# Sheet1.net
KiCad netlist of a schematic drawn in Altium Designer
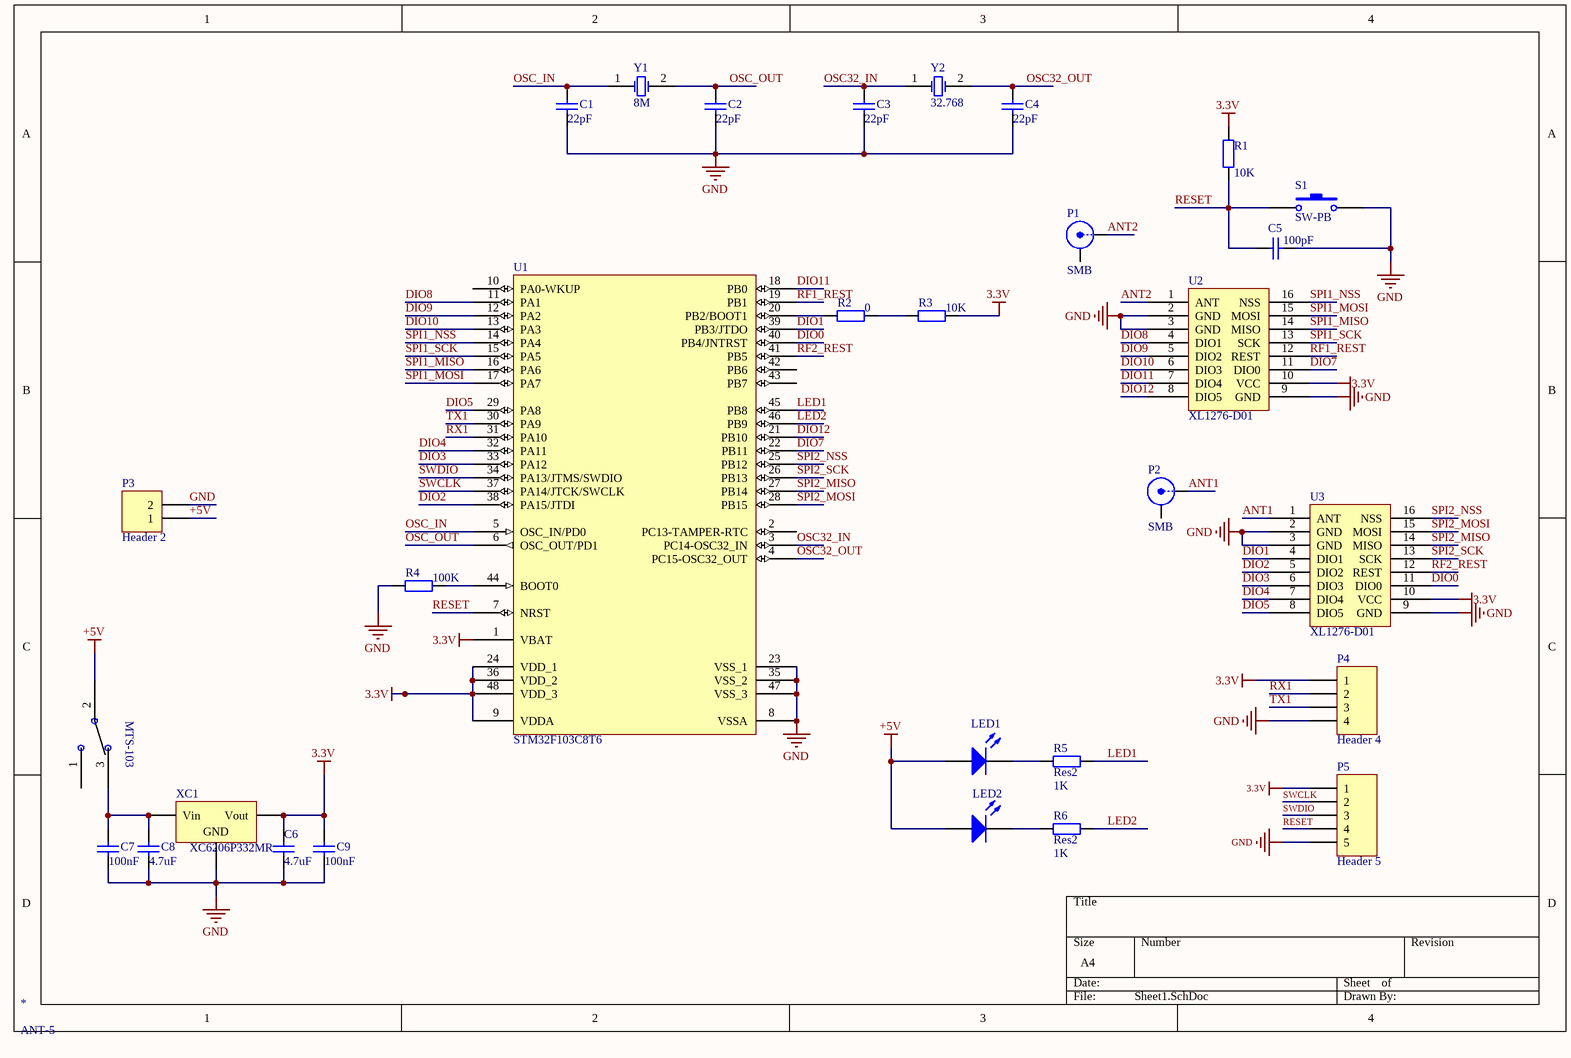
[diagram p0: Sheet1.SchDoc]

(export (version "E")
  (design (tool "Eeschema 10.0.6"))
  (components
    (comp (ref "*") (value "ANT-5") (libsource (lib "Schlib1") (part "ANT-5")))
    (comp (ref "C1")
      (value "22pF")
      (footprint "1608[0603]")
      (description "Capacitor (Semiconductor SIM Model)")
      (fields (field (name "Comment") "Cap Semi") (field (name "PUBLISHER") "Altium Limited"))
      (libsource (lib "Miscellaneous Devices") (part "Cap Semi"))
    )
    (comp (ref "C2")
      (value "22pF")
      (footprint "1608[0603]")
      (description "Capacitor (Semiconductor SIM Model)")
      (fields (field (name "Comment") "Cap Semi") (field (name "PUBLISHER") "Altium Limited"))
      (libsource (lib "Miscellaneous Devices") (part "Cap Semi"))
    )
    (comp (ref "C3")
      (value "22pF")
      (footprint "1608[0603]")
      (description "Capacitor (Semiconductor SIM Model)")
      (fields (field (name "Comment") "Cap Semi") (field (name "PUBLISHER") "Altium Limited"))
      (libsource (lib "Miscellaneous Devices") (part "Cap Semi"))
    )
    (comp (ref "C4")
      (value "22pF")
      (footprint "1608[0603]")
      (description "Capacitor (Semiconductor SIM Model)")
      (fields (field (name "Comment") "Cap Semi") (field (name "PUBLISHER") "Altium Limited"))
      (libsource (lib "Miscellaneous Devices") (part "Cap Semi"))
    )
    (comp (ref "C5")
      (value "100pF")
      (footprint "1608[0603]")
      (description "Capacitor (Semiconductor SIM Model)")
      (fields (field (name "Comment") "Cap Semi") (field (name "PUBLISHER") "Altium Limited"))
      (libsource (lib "Miscellaneous Devices") (part "Cap Semi"))
    )
    (comp (ref "C6")
      (value "4.7uF")
      (footprint "1608[0603]")
      (description "Capacitor (Semiconductor SIM Model)")
      (fields (field (name "Comment") "Cap Semi") (field (name "PUBLISHER") "Altium Limited"))
      (libsource (lib "Miscellaneous Devices") (part "Cap Semi"))
    )
    (comp (ref "C7")
      (value "100nF")
      (footprint "1608[0603]")
      (description "Capacitor (Semiconductor SIM Model)")
      (fields (field (name "Comment") "Cap Semi") (field (name "PUBLISHER") "Altium Limited"))
      (libsource (lib "Miscellaneous Devices") (part "Cap Semi"))
    )
    (comp (ref "C8")
      (value "4.7uF")
      (footprint "1608[0603]")
      (description "Capacitor (Semiconductor SIM Model)")
      (fields (field (name "Comment") "Cap Semi") (field (name "PUBLISHER") "Altium Limited"))
      (libsource (lib "Miscellaneous Devices") (part "Cap Semi"))
    )
    (comp (ref "C9")
      (value "100nF")
      (footprint "1608[0603]")
      (description "Capacitor (Semiconductor SIM Model)")
      (fields (field (name "Comment") "Cap Semi") (field (name "PUBLISHER") "Altium Limited"))
      (libsource (lib "Miscellaneous Devices") (part "Cap Semi"))
    )
    (comp (ref "LED1")
      (value "LED2")
      (footprint "3.2X1.6X1.1")
      (description "Typical RED, GREEN, YELLOW, AMBER GaAs LED")
      (fields (field (name "PUBLISHER") "Altium Limited"))
      (libsource (lib "Miscellaneous Devices") (part "LED2"))
    )
    (comp (ref "LED2")
      (value "LED2")
      (footprint "3.2X1.6X1.1")
      (description "Typical RED, GREEN, YELLOW, AMBER GaAs LED")
      (fields (field (name "PUBLISHER") "Altium Limited"))
      (libsource (lib "Miscellaneous Devices") (part "LED2"))
    )
    (comp (ref "MTS-1")
      (value "MTS-103")
      (footprint "PcbLib1:MTS-103")
      (libsource (lib "Schlib1") (part "MTS-103"))
    )
    (comp (ref "P1")
      (value "SMB")
      (footprint "SMB_V-RJ45")
      (description "SMB Straight Connector")
      (fields (field (name "PUBLISHER") "Altium Limited"))
      (libsource (lib "Miscellaneous Connectors") (part "SMB"))
    )
    (comp (ref "P2")
      (value "SMB")
      (footprint "SMB_V-RJ45")
      (description "SMB Straight Connector")
      (fields (field (name "PUBLISHER") "Altium Limited"))
      (libsource (lib "Miscellaneous Connectors") (part "SMB"))
    )
    (comp (ref "P3")
      (value "Header 2")
      (footprint "HDR1X2")
      (description "Header, 2-Pin")
      (fields (field (name "PUBLISHER") "Altium Limited"))
      (libsource (lib "Miscellaneous Connectors") (part "Header 2"))
    )
    (comp (ref "P4")
      (value "Header 4")
      (footprint "HDR1X4")
      (description "Header, 4-Pin")
      (fields (field (name "PUBLISHER") "Altium Limited"))
      (libsource (lib "Miscellaneous Connectors") (part "Header 4"))
    )
    (comp (ref "P5")
      (value "Header 5")
      (footprint "HDR1X5")
      (description "Header, 5-Pin")
      (fields (field (name "PUBLISHER") "Altium Limited"))
      (libsource (lib "Miscellaneous Connectors") (part "Header 5"))
    )
    (comp (ref "R1")
      (value "10K")
      (footprint "1608[0603]")
      (description "Resistor")
      (fields (field (name "Comment") "Res2") (field (name "PUBLISHER") "Altium Limited"))
      (libsource (lib "") (part "Res2_1"))
    )
    (comp (ref "R2")
      (value "0")
      (footprint "1608[0603]")
      (description "Resistor")
      (fields (field (name "Comment") "Res2") (field (name "PUBLISHER") "Altium Limited"))
      (libsource (lib "Miscellaneous Devices") (part "Res2"))
    )
    (comp (ref "R3")
      (value "10K")
      (footprint "1608[0603]")
      (description "Resistor")
      (fields (field (name "Comment") "Res2") (field (name "PUBLISHER") "Altium Limited"))
      (libsource (lib "Miscellaneous Devices") (part "Res2"))
    )
    (comp (ref "R4")
      (value "100K")
      (footprint "1608[0603]")
      (description "Resistor")
      (fields (field (name "Comment") "Res2") (field (name "PUBLISHER") "Altium Limited"))
      (libsource (lib "Miscellaneous Devices") (part "Res2"))
    )
    (comp (ref "R5")
      (value "Res2")
      (footprint "1608[0603]")
      (description "Resistor")
      (fields (field (name "ALTIUM_VALUE") "1K") (field (name "PUBLISHER") "Altium Limited"))
      (libsource (lib "Miscellaneous Devices") (part "Res2"))
    )
    (comp (ref "R6")
      (value "Res2")
      (footprint "1608[0603]")
      (description "Resistor")
      (fields (field (name "ALTIUM_VALUE") "1K") (field (name "PUBLISHER") "Altium Limited"))
      (libsource (lib "Miscellaneous Devices") (part "Res2"))
    )
    (comp (ref "S1")
      (value "SW-PB")
      (footprint "SPST-2")
      (description "Switch")
      (fields (field (name "PUBLISHER") "Altium Limited"))
      (libsource (lib "Miscellaneous Devices") (part "SW-PB"))
    )
    (comp (ref "U1")
      (value "STM32F103C8T6")
      (footprint "LQFP48_N")
      (description "STM32 ARM-based 32-bit MCU with 64 Kbytes Flash, 48-pin LQFP, Industrial Temperature")
      (fields (field (name "PUBLISHER") "Altium Limited"))
      (libsource (lib "ST Microcontroller 32-Bit STM32") (part "STM32F103C8T6"))
    )
    (comp (ref "U2")
      (value "XL1276-D01")
      (footprint "XL1278-DO1")
      (libsource (lib "Schlib1") (part "XL1276-D01"))
    )
    (comp (ref "U3")
      (value "XL1276-D01")
      (footprint "XL1278-DO1")
      (libsource (lib "Schlib1") (part "XL1276-D01"))
    )
    (comp (ref "XC1")
      (value "XC6206P332MR")
      (footprint "SOT89L")
      (description "Voltage Regulator")
      (fields (field (name "PUBLISHER") "Altium Limited"))
      (libsource (lib "Miscellaneous Devices") (part "Volt Reg"))
    )
    (comp (ref "Y1")
      (value "8M")
      (footprint "HC-48SMD")
      (description "Crystal Oscillator")
      (fields (field (name "PUBLISHER") "Altium Limited"))
      (libsource (lib "Miscellaneous Devices") (part "XTAL"))
    )
    (comp (ref "Y2")
      (value "32.768")
      (footprint "FC135")
      (description "Crystal Oscillator")
      (fields (field (name "PUBLISHER") "Altium Limited"))
      (libsource (lib "Miscellaneous Devices") (part "XTAL"))
    )
  )
  (nets
    (net (code "1") (name "+5V") (class "Default")
      (node (ref "LED1") (pin "1") (pinfunction "A_1") (pintype "passive"))
      (node (ref "LED2") (pin "1") (pinfunction "A_1") (pintype "passive"))
      (node (ref "MTS-1") (pin "2") (pinfunction "2_2") (pintype "passive"))
      (node (ref "P3") (pin "1") (pinfunction "1_1") (pintype "passive"))
    )
    (net (code "2") (name "/ANT1") (class "Default")
      (node (ref "P2") (pin "1") (pinfunction "X_1") (pintype "passive"))
      (node (ref "U3") (pin "1") (pinfunction "ANT_1") (pintype "passive"))
    )
    (net (code "3") (name "/ANT2") (class "Default")
      (node (ref "P1") (pin "1") (pinfunction "X_1") (pintype "passive"))
      (node (ref "U2") (pin "1") (pinfunction "ANT_1") (pintype "passive"))
    )
    (net (code "4") (name "/DIO0") (class "Default")
      (node (ref "U1") (pin "40") (pinfunction "PB4/JNTRST_40") (pintype "bidirectional"))
      (node (ref "U3") (pin "11") (pinfunction "DIO0_11") (pintype "passive"))
    )
    (net (code "5") (name "/DIO1") (class "Default")
      (node (ref "U1") (pin "39") (pinfunction "PB3/JTDO_39") (pintype "bidirectional"))
      (node (ref "U3") (pin "4") (pinfunction "DIO1_4") (pintype "passive"))
    )
    (net (code "6") (name "/DIO2") (class "Default")
      (node (ref "U1") (pin "38") (pinfunction "PA15/JTDI_38") (pintype "bidirectional"))
      (node (ref "U3") (pin "5") (pinfunction "DIO2_5") (pintype "passive"))
    )
    (net (code "7") (name "/DIO3") (class "Default")
      (node (ref "U1") (pin "33") (pinfunction "PA12_33") (pintype "bidirectional"))
      (node (ref "U3") (pin "6") (pinfunction "DIO3_6") (pintype "passive"))
    )
    (net (code "8") (name "/DIO4") (class "Default")
      (node (ref "U1") (pin "32") (pinfunction "PA11_32") (pintype "bidirectional"))
      (node (ref "U3") (pin "7") (pinfunction "DIO4_7") (pintype "passive"))
    )
    (net (code "9") (name "/DIO5") (class "Default")
      (node (ref "U1") (pin "29") (pinfunction "PA8_29") (pintype "bidirectional"))
      (node (ref "U3") (pin "8") (pinfunction "DIO5_8") (pintype "passive"))
    )
    (net (code "10") (name "/DIO7") (class "Default")
      (node (ref "U1") (pin "22") (pinfunction "PB11_22") (pintype "bidirectional"))
      (node (ref "U2") (pin "11") (pinfunction "DIO0_11") (pintype "passive"))
    )
    (net (code "11") (name "/DIO8") (class "Default")
      (node (ref "U1") (pin "11") (pinfunction "PA1_11") (pintype "bidirectional"))
      (node (ref "U2") (pin "4") (pinfunction "DIO1_4") (pintype "passive"))
    )
    (net (code "12") (name "/DIO9") (class "Default")
      (node (ref "U1") (pin "12") (pinfunction "PA2_12") (pintype "bidirectional"))
      (node (ref "U2") (pin "5") (pinfunction "DIO2_5") (pintype "passive"))
    )
    (net (code "13") (name "/DIO10") (class "Default")
      (node (ref "U1") (pin "13") (pinfunction "PA3_13") (pintype "bidirectional"))
      (node (ref "U2") (pin "6") (pinfunction "DIO3_6") (pintype "passive"))
    )
    (net (code "14") (name "/DIO11") (class "Default")
      (node (ref "U1") (pin "18") (pinfunction "PB0_18") (pintype "bidirectional"))
      (node (ref "U2") (pin "7") (pinfunction "DIO4_7") (pintype "passive"))
    )
    (net (code "15") (name "/DIO12") (class "Default")
      (node (ref "U1") (pin "21") (pinfunction "PB10_21") (pintype "bidirectional"))
      (node (ref "U2") (pin "8") (pinfunction "DIO5_8") (pintype "passive"))
    )
    (net (code "16") (name "/LED1") (class "Default")
      (node (ref "R5") (pin "2") (pinfunction "2_2") (pintype "passive"))
      (node (ref "U1") (pin "45") (pinfunction "PB8_45") (pintype "bidirectional"))
    )
    (net (code "17") (name "/LED2") (class "Default")
      (node (ref "R6") (pin "2") (pinfunction "2_2") (pintype "passive"))
      (node (ref "U1") (pin "46") (pinfunction "PB9_46") (pintype "bidirectional"))
    )
    (net (code "18") (name "/OSC32_IN") (class "Default")
      (node (ref "C3") (pin "2") (pinfunction "2_2") (pintype "passive"))
      (node (ref "U1") (pin "3") (pinfunction "PC14-OSC32_IN_3") (pintype "bidirectional"))
      (node (ref "Y2") (pin "1") (pinfunction "OSC1_1") (pintype "passive"))
    )
    (net (code "19") (name "/OSC32_OUT") (class "Default")
      (node (ref "C4") (pin "2") (pinfunction "2_2") (pintype "passive"))
      (node (ref "U1") (pin "4") (pinfunction "PC15-OSC32_OUT_4") (pintype "bidirectional"))
      (node (ref "Y2") (pin "2") (pinfunction "OSC2_2") (pintype "passive"))
    )
    (net (code "20") (name "/OSC_IN") (class "Default")
      (node (ref "C1") (pin "2") (pinfunction "2_2") (pintype "passive"))
      (node (ref "U1") (pin "5") (pinfunction "OSC_IN/PD0_5") (pintype "input"))
      (node (ref "Y1") (pin "1") (pinfunction "OSC1_1") (pintype "passive"))
    )
    (net (code "21") (name "/OSC_OUT") (class "Default")
      (node (ref "C2") (pin "2") (pinfunction "2_2") (pintype "passive"))
      (node (ref "U1") (pin "6") (pinfunction "OSC_OUT/PD1_6") (pintype "output"))
      (node (ref "Y1") (pin "2") (pinfunction "OSC2_2") (pintype "passive"))
    )
    (net (code "22") (name "/RESET") (class "Default")
      (node (ref "C5") (pin "1") (pinfunction "1_1") (pintype "passive"))
      (node (ref "P5") (pin "4") (pinfunction "4_4") (pintype "passive"))
      (node (ref "R1") (pin "2") (pinfunction "2_2") (pintype "passive"))
      (node (ref "S1") (pin "1") (pinfunction "1_1") (pintype "passive"))
      (node (ref "U1") (pin "7") (pinfunction "NRST_7") (pintype "bidirectional"))
    )
    (net (code "23") (name "/RF1_REST") (class "Default")
      (node (ref "U1") (pin "19") (pinfunction "PB1_19") (pintype "bidirectional"))
      (node (ref "U2") (pin "12") (pinfunction "REST_12") (pintype "passive"))
    )
    (net (code "24") (name "/RF2_REST") (class "Default")
      (node (ref "U1") (pin "41") (pinfunction "PB5_41") (pintype "bidirectional"))
      (node (ref "U3") (pin "12") (pinfunction "REST_12") (pintype "passive"))
    )
    (net (code "25") (name "/RX1") (class "Default")
      (node (ref "P4") (pin "2") (pinfunction "2_2") (pintype "passive"))
      (node (ref "U1") (pin "31") (pinfunction "PA10_31") (pintype "bidirectional"))
    )
    (net (code "26") (name "/SPI1_MISO") (class "Default")
      (node (ref "U1") (pin "16") (pinfunction "PA6_16") (pintype "bidirectional"))
      (node (ref "U2") (pin "14") (pinfunction "MISO_14") (pintype "passive"))
    )
    (net (code "27") (name "/SPI1_MOSI") (class "Default")
      (node (ref "U1") (pin "17") (pinfunction "PA7_17") (pintype "bidirectional"))
      (node (ref "U2") (pin "15") (pinfunction "MOSI_15") (pintype "passive"))
    )
    (net (code "28") (name "/SPI1_NSS") (class "Default")
      (node (ref "U1") (pin "14") (pinfunction "PA4_14") (pintype "bidirectional"))
      (node (ref "U2") (pin "16") (pinfunction "NSS_16") (pintype "passive"))
    )
    (net (code "29") (name "/SPI1_SCK") (class "Default")
      (node (ref "U1") (pin "15") (pinfunction "PA5_15") (pintype "bidirectional"))
      (node (ref "U2") (pin "13") (pinfunction "SCK_13") (pintype "passive"))
    )
    (net (code "30") (name "/SPI2_MISO") (class "Default")
      (node (ref "U1") (pin "27") (pinfunction "PB14_27") (pintype "bidirectional"))
      (node (ref "U3") (pin "14") (pinfunction "MISO_14") (pintype "passive"))
    )
    (net (code "31") (name "/SPI2_MOSI") (class "Default")
      (node (ref "U1") (pin "28") (pinfunction "PB15_28") (pintype "bidirectional"))
      (node (ref "U3") (pin "15") (pinfunction "MOSI_15") (pintype "passive"))
    )
    (net (code "32") (name "/SPI2_NSS") (class "Default")
      (node (ref "U1") (pin "25") (pinfunction "PB12_25") (pintype "bidirectional"))
      (node (ref "U3") (pin "16") (pinfunction "NSS_16") (pintype "passive"))
    )
    (net (code "33") (name "/SPI2_SCK") (class "Default")
      (node (ref "U1") (pin "26") (pinfunction "PB13_26") (pintype "bidirectional"))
      (node (ref "U3") (pin "13") (pinfunction "SCK_13") (pintype "passive"))
    )
    (net (code "34") (name "/SWCLK") (class "Default")
      (node (ref "P5") (pin "2") (pinfunction "2_2") (pintype "passive"))
      (node (ref "U1") (pin "37") (pinfunction "PA14/JTCK/SWCLK_37") (pintype "bidirectional"))
    )
    (net (code "35") (name "/SWDIO") (class "Default")
      (node (ref "P5") (pin "3") (pinfunction "3_3") (pintype "passive"))
      (node (ref "U1") (pin "34") (pinfunction "PA13/JTMS/SWDIO_34") (pintype "bidirectional"))
    )
    (net (code "36") (name "/TX1") (class "Default")
      (node (ref "P4") (pin "3") (pinfunction "3_3") (pintype "passive"))
      (node (ref "U1") (pin "30") (pinfunction "PA9_30") (pintype "bidirectional"))
    )
    (net (code "37") (name "3.3V") (class "Default")
      (node (ref "C6") (pin "2") (pinfunction "2_2") (pintype "passive"))
      (node (ref "C9") (pin "2") (pinfunction "2_2") (pintype "passive"))
      (node (ref "P4") (pin "1") (pinfunction "1_1") (pintype "passive"))
      (node (ref "P5") (pin "1") (pinfunction "1_1") (pintype "passive"))
      (node (ref "R1") (pin "1") (pinfunction "1_1") (pintype "passive"))
      (node (ref "R3") (pin "2") (pinfunction "2_2") (pintype "passive"))
      (node (ref "U1") (pin "1") (pinfunction "VBAT_1") (pintype "power_in"))
      (node (ref "U1") (pin "24") (pinfunction "VDD_1_24") (pintype "power_in"))
      (node (ref "U1") (pin "36") (pinfunction "VDD_2_36") (pintype "power_in"))
      (node (ref "U1") (pin "48") (pinfunction "VDD_3_48") (pintype "power_in"))
      (node (ref "U1") (pin "9") (pinfunction "VDDA_9") (pintype "power_in"))
      (node (ref "U2") (pin "10") (pinfunction "VCC_10") (pintype "passive"))
      (node (ref "U3") (pin "10") (pinfunction "VCC_10") (pintype "passive"))
      (node (ref "XC1") (pin "3") (pinfunction "Vout_3") (pintype "passive"))
    )
    (net (code "38") (name "GND") (class "Default")
      (node (ref "C1") (pin "1") (pinfunction "1_1") (pintype "passive"))
      (node (ref "C2") (pin "1") (pinfunction "1_1") (pintype "passive"))
      (node (ref "C3") (pin "1") (pinfunction "1_1") (pintype "passive"))
      (node (ref "C4") (pin "1") (pinfunction "1_1") (pintype "passive"))
      (node (ref "C5") (pin "2") (pinfunction "2_2") (pintype "passive"))
      (node (ref "C6") (pin "1") (pinfunction "1_1") (pintype "passive"))
      (node (ref "C7") (pin "1") (pinfunction "1_1") (pintype "passive"))
      (node (ref "C8") (pin "1") (pinfunction "1_1") (pintype "passive"))
      (node (ref "C9") (pin "1") (pinfunction "1_1") (pintype "passive"))
      (node (ref "P3") (pin "2") (pinfunction "2_2") (pintype "passive"))
      (node (ref "P4") (pin "4") (pinfunction "4_4") (pintype "passive"))
      (node (ref "P5") (pin "5") (pinfunction "5_5") (pintype "passive"))
      (node (ref "R4") (pin "1") (pinfunction "1_1") (pintype "passive"))
      (node (ref "S1") (pin "2") (pinfunction "2_2") (pintype "passive"))
      (node (ref "U1") (pin "23") (pinfunction "VSS_1_23") (pintype "power_in"))
      (node (ref "U1") (pin "35") (pinfunction "VSS_2_35") (pintype "power_in"))
      (node (ref "U1") (pin "47") (pinfunction "VSS_3_47") (pintype "power_in"))
      (node (ref "U1") (pin "8") (pinfunction "VSSA_8") (pintype "power_in"))
      (node (ref "U2") (pin "2") (pinfunction "GND_2") (pintype "passive"))
      (node (ref "U2") (pin "3") (pinfunction "GND_3") (pintype "passive"))
      (node (ref "U2") (pin "9") (pinfunction "GND_9") (pintype "passive"))
      (node (ref "U3") (pin "2") (pinfunction "GND_2") (pintype "passive"))
      (node (ref "U3") (pin "3") (pinfunction "GND_3") (pintype "passive"))
      (node (ref "U3") (pin "9") (pinfunction "GND_9") (pintype "passive"))
      (node (ref "XC1") (pin "2") (pinfunction "GND_2") (pintype "passive"))
    )
    (net (code "39") (name "Net-(LED1-K)") (class "Default")
      (node (ref "LED1") (pin "2") (pinfunction "K_2") (pintype "passive"))
      (node (ref "R5") (pin "1") (pinfunction "1_1") (pintype "passive"))
    )
    (net (code "40") (name "Net-(LED2-K)") (class "Default")
      (node (ref "LED2") (pin "2") (pinfunction "K_2") (pintype "passive"))
      (node (ref "R6") (pin "1") (pinfunction "1_1") (pintype "passive"))
    )
    (net (code "41") (name "Net-(R2-Pad2)") (class "Default")
      (node (ref "R2") (pin "2") (pinfunction "2_2") (pintype "passive"))
      (node (ref "R3") (pin "1") (pinfunction "1_1") (pintype "passive"))
    )
    (net (code "42") (name "Net-(U1-BOOT0)") (class "Default")
      (node (ref "R4") (pin "2") (pinfunction "2_2") (pintype "passive"))
      (node (ref "U1") (pin "44") (pinfunction "BOOT0_44") (pintype "input"))
    )
    (net (code "43") (name "Net-(U1-PB2{slash}BOOT1)") (class "Default")
      (node (ref "R2") (pin "1") (pinfunction "1_1") (pintype "passive"))
      (node (ref "U1") (pin "20") (pinfunction "PB2/BOOT1_20") (pintype "bidirectional"))
    )
    (net (code "44") (name "Net-(XC1-Vin)") (class "Default")
      (node (ref "C7") (pin "2") (pinfunction "2_2") (pintype "passive"))
      (node (ref "C8") (pin "2") (pinfunction "2_2") (pintype "passive"))
      (node (ref "MTS-1") (pin "3") (pinfunction "3_3") (pintype "passive"))
      (node (ref "XC1") (pin "1") (pinfunction "Vin_1") (pintype "passive"))
    )
    (net (code "45") (name "unconnected-(MTS-1-Pad1)") (class "Default")
      (node (ref "MTS-1") (pin "1") (pinfunction "1_1") (pintype "passive"))
    )
    (net (code "46") (name "unconnected-(P1-Y-Pad2)") (class "Default")
      (node (ref "P1") (pin "2") (pinfunction "Y_2") (pintype "passive"))
    )
    (net (code "47") (name "unconnected-(P2-Y-Pad2)") (class "Default")
      (node (ref "P2") (pin "2") (pinfunction "Y_2") (pintype "passive"))
    )
    (net (code "48") (name "unconnected-(U1-PA0-WKUP-Pad10)") (class "Default")
      (node (ref "U1") (pin "10") (pinfunction "PA0-WKUP_10") (pintype "bidirectional"))
    )
    (net (code "49") (name "unconnected-(U1-PB6-Pad42)") (class "Default")
      (node (ref "U1") (pin "42") (pinfunction "PB6_42") (pintype "bidirectional"))
    )
    (net (code "50") (name "unconnected-(U1-PB7-Pad43)") (class "Default")
      (node (ref "U1") (pin "43") (pinfunction "PB7_43") (pintype "bidirectional"))
    )
    (net (code "51") (name "unconnected-(U1-PC13-TAMPER-RTC-Pad2)") (class "Default")
      (node (ref "U1") (pin "2") (pinfunction "PC13-TAMPER-RTC_2") (pintype "bidirectional"))
    )
  )
)
